# USB_Hub.net
KiCad netlist of a schematic drawn in EAGLE
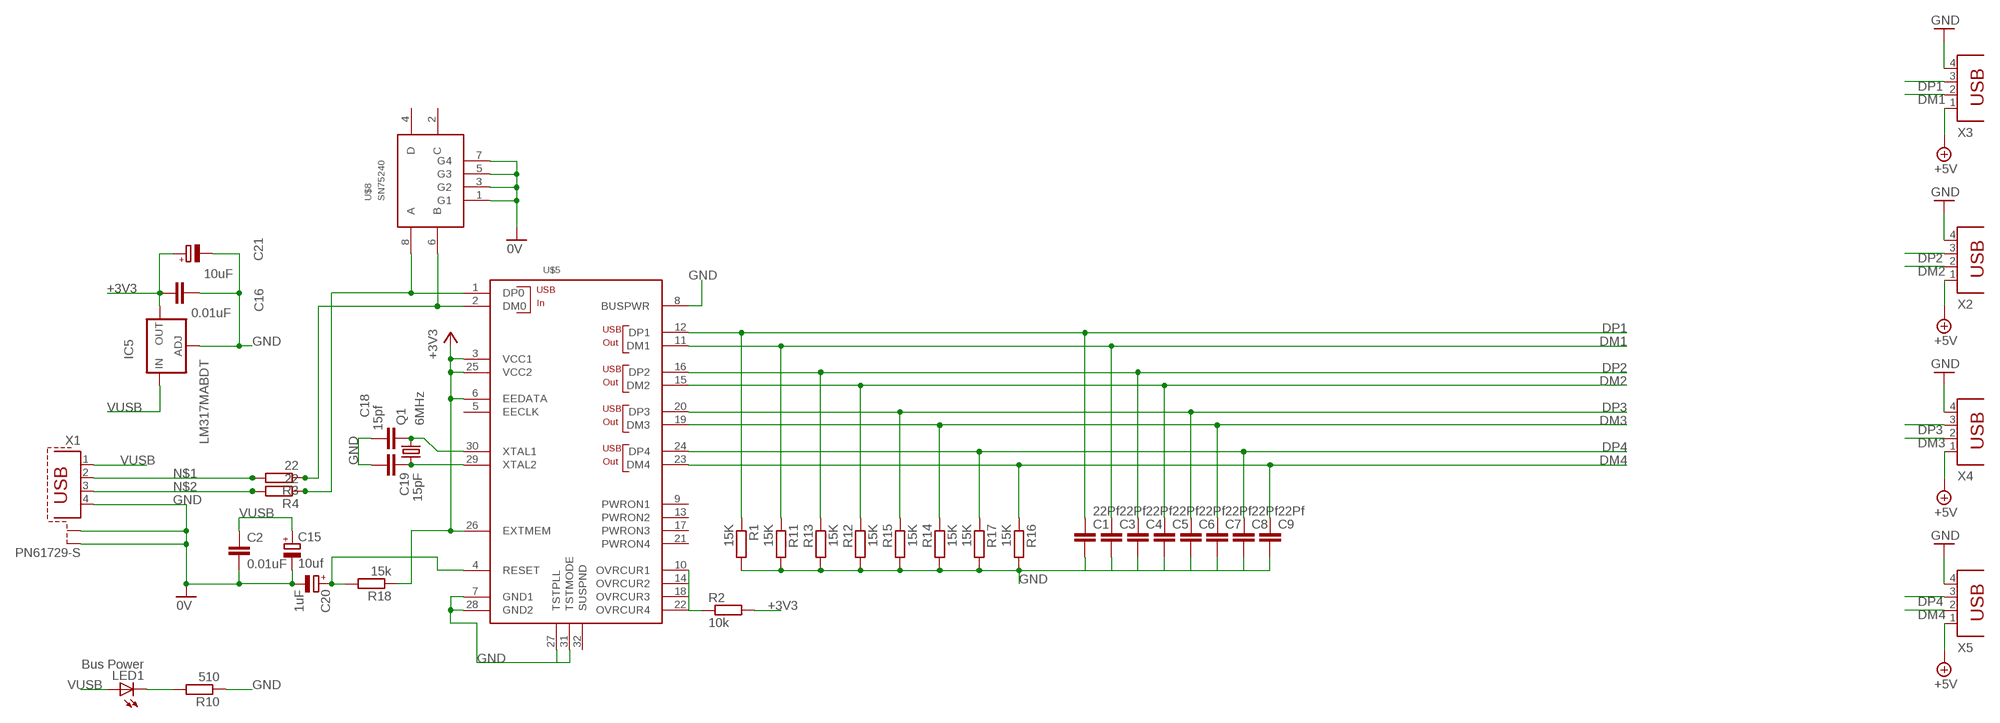
[diagram p0: schematic, sheet 1]

(export (version "E")
  (design (tool "Eeschema 10.0.6"))
  (components
    (comp (ref "C1")
      (value "22Pf")
      (footprint "eagle-import:C0805")
      (libsource (lib "eagle-import") (part "C-EUC0805"))
    )
    (comp (ref "C2")
      (value "0.01uF")
      (footprint "eagle-import:C0805")
      (libsource (lib "eagle-import") (part "C-EUC0805"))
    )
    (comp (ref "C3")
      (value "22Pf")
      (footprint "eagle-import:C0805")
      (libsource (lib "eagle-import") (part "C-EUC0805"))
    )
    (comp (ref "C4")
      (value "22Pf")
      (footprint "eagle-import:C0805")
      (libsource (lib "eagle-import") (part "C-EUC0805"))
    )
    (comp (ref "C5")
      (value "22Pf")
      (footprint "eagle-import:C0805")
      (libsource (lib "eagle-import") (part "C-EUC0805"))
    )
    (comp (ref "C6")
      (value "22Pf")
      (footprint "eagle-import:C0805")
      (libsource (lib "eagle-import") (part "C-EUC0805"))
    )
    (comp (ref "C7")
      (value "22Pf")
      (footprint "eagle-import:C0805")
      (libsource (lib "eagle-import") (part "C-EUC0805"))
    )
    (comp (ref "C8")
      (value "22Pf")
      (footprint "eagle-import:C0805")
      (libsource (lib "eagle-import") (part "C-EUC0805"))
    )
    (comp (ref "C9")
      (value "22Pf")
      (footprint "eagle-import:C0805")
      (libsource (lib "eagle-import") (part "C-EUC0805"))
    )
    (comp (ref "C15")
      (value "10uf")
      (footprint "eagle-import:E2,5-6")
      (libsource (lib "eagle-import") (part "CPOL-EUE2.5-6"))
    )
    (comp (ref "C16")
      (value "0.01uF")
      (footprint "eagle-import:C0805")
      (libsource (lib "eagle-import") (part "C-EUC0805"))
    )
    (comp (ref "C18")
      (value "15pf")
      (footprint "eagle-import:C0805")
      (libsource (lib "eagle-import") (part "C-EUC0805"))
    )
    (comp (ref "C19")
      (value "15pF")
      (footprint "eagle-import:C0805")
      (libsource (lib "eagle-import") (part "C-EUC0805"))
    )
    (comp (ref "C20")
      (value "1uF")
      (footprint "eagle-import:E2,5-6")
      (libsource (lib "eagle-import") (part "CPOL-EUE2.5-6"))
    )
    (comp (ref "C21")
      (value "10uF")
      (footprint "eagle-import:E2,5-6")
      (libsource (lib "eagle-import") (part "CPOL-EUE2.5-6"))
    )
    (comp (ref "IC5")
      (value "LM317MABDT")
      (footprint "eagle-import:DPACK")
      (libsource (lib "eagle-import") (part "v-reg_LM317?MABDT"))
    )
    (comp (ref "LED1")
      (value "Bus Power")
      (footprint "eagle-import:CHIP-LED0805")
      (libsource (lib "eagle-import") (part "LEDCHIP-LED0805"))
    )
    (comp (ref "Q1")
      (value "6MHz")
      (footprint "eagle-import:HC49UP")
      (libsource (lib "eagle-import") (part "CRYSTALHC49UP"))
    )
    (comp (ref "R1")
      (value "15K")
      (footprint "eagle-import:R0805")
      (libsource (lib "eagle-import") (part "R-EU_R0805"))
    )
    (comp (ref "R2")
      (value "10k")
      (footprint "eagle-import:R0805")
      (libsource (lib "eagle-import") (part "R-EU_R0805"))
    )
    (comp (ref "R3")
      (value "22")
      (footprint "eagle-import:R0805")
      (libsource (lib "eagle-import") (part "R-EU_R0805"))
    )
    (comp (ref "R4")
      (value "22")
      (footprint "eagle-import:R0805")
      (libsource (lib "eagle-import") (part "R-EU_R0805"))
    )
    (comp (ref "R10")
      (value "510")
      (footprint "eagle-import:R0805")
      (libsource (lib "eagle-import") (part "R-EU_R0805"))
    )
    (comp (ref "R11")
      (value "15K")
      (footprint "eagle-import:R0805")
      (libsource (lib "eagle-import") (part "R-EU_R0805"))
    )
    (comp (ref "R12")
      (value "15K")
      (footprint "eagle-import:R0805")
      (libsource (lib "eagle-import") (part "R-EU_R0805"))
    )
    (comp (ref "R13")
      (value "15K")
      (footprint "eagle-import:R0805")
      (libsource (lib "eagle-import") (part "R-EU_R0805"))
    )
    (comp (ref "R14")
      (value "15K")
      (footprint "eagle-import:R0805")
      (libsource (lib "eagle-import") (part "R-EU_R0805"))
    )
    (comp (ref "R15")
      (value "15K")
      (footprint "eagle-import:R0805")
      (libsource (lib "eagle-import") (part "R-EU_R0805"))
    )
    (comp (ref "R16")
      (value "15K")
      (footprint "eagle-import:R0805")
      (libsource (lib "eagle-import") (part "R-EU_R0805"))
    )
    (comp (ref "R17")
      (value "15K")
      (footprint "eagle-import:R0805")
      (libsource (lib "eagle-import") (part "R-EU_R0805"))
    )
    (comp (ref "R18")
      (value "15k")
      (footprint "eagle-import:R0805")
      (libsource (lib "eagle-import") (part "R-EU_R0805"))
    )
    (comp (ref "U$5")
      (value "TUSB2046")
      (footprint "eagle-import:LQFP-32")
      (libsource (lib "eagle-import") (part "TUSB2046"))
    )
    (comp (ref "U$8")
      (value "SN75240")
      (footprint "eagle-import:TSSOP8")
      (libsource (lib "eagle-import") (part "SN75240"))
    )
    (comp (ref "X1")
      (value "PN61729-S")
      (footprint "eagle-import:PN61729-S")
      (libsource (lib "eagle-import") (part "PN61729-S"))
    )
    (comp (ref "X2")
      (value "PN87520")
      (footprint "eagle-import:PN87520")
      (libsource (lib "eagle-import") (part "PN87520"))
    )
    (comp (ref "X3")
      (value "PN87520")
      (footprint "eagle-import:PN87520")
      (libsource (lib "eagle-import") (part "PN87520"))
    )
    (comp (ref "X4")
      (value "PN87520")
      (footprint "eagle-import:PN87520")
      (libsource (lib "eagle-import") (part "PN87520"))
    )
    (comp (ref "X5")
      (value "PN87520")
      (footprint "eagle-import:PN87520")
      (libsource (lib "eagle-import") (part "PN87520"))
    )
  )
  (nets
    (net (code "1") (name "+3V3") (class "Default")
      (node (ref "C16") (pin "1") (pinfunction "1_1") (pintype "passive"))
      (node (ref "C21") (pin "+") (pinfunction "+_+") (pintype "passive"))
      (node (ref "IC5") (pin "4") (pinfunction "OUT_4") (pintype "passive"))
      (node (ref "R18") (pin "1") (pinfunction "1_1") (pintype "passive"))
      (node (ref "R2") (pin "2") (pinfunction "2_2") (pintype "passive"))
      (node (ref "U$5") (pin "25") (pinfunction "VCC2_25") (pintype "bidirectional"))
      (node (ref "U$5") (pin "26") (pinfunction "EXTMEM_26") (pintype "bidirectional"))
      (node (ref "U$5") (pin "3") (pinfunction "VCC1_3") (pintype "bidirectional"))
      (node (ref "U$5") (pin "6") (pinfunction "EEDATA_6") (pintype "bidirectional"))
    )
    (net (code "2") (name "+5V") (class "Default")
      (node (ref "X2") (pin "1") (pinfunction "1_1") (pintype "passive"))
      (node (ref "X3") (pin "1") (pinfunction "1_1") (pintype "passive"))
      (node (ref "X4") (pin "1") (pinfunction "1_1") (pintype "passive"))
      (node (ref "X5") (pin "1") (pinfunction "1_1") (pintype "passive"))
    )
    (net (code "3") (name "/DM1") (class "Default")
      (node (ref "C3") (pin "1") (pinfunction "1_1") (pintype "passive"))
      (node (ref "R11") (pin "1") (pinfunction "1_1") (pintype "passive"))
      (node (ref "U$5") (pin "11") (pinfunction "DM1_11") (pintype "bidirectional"))
      (node (ref "X3") (pin "2") (pinfunction "2_2") (pintype "passive"))
    )
    (net (code "4") (name "/DM2") (class "Default")
      (node (ref "C5") (pin "1") (pinfunction "1_1") (pintype "passive"))
      (node (ref "R12") (pin "1") (pinfunction "1_1") (pintype "passive"))
      (node (ref "U$5") (pin "15") (pinfunction "DM2_15") (pintype "bidirectional"))
      (node (ref "X2") (pin "2") (pinfunction "2_2") (pintype "passive"))
    )
    (net (code "5") (name "/DM3") (class "Default")
      (node (ref "C7") (pin "1") (pinfunction "1_1") (pintype "passive"))
      (node (ref "R14") (pin "1") (pinfunction "1_1") (pintype "passive"))
      (node (ref "U$5") (pin "19") (pinfunction "DM3_19") (pintype "bidirectional"))
      (node (ref "X4") (pin "2") (pinfunction "2_2") (pintype "passive"))
    )
    (net (code "6") (name "/DM4") (class "Default")
      (node (ref "C9") (pin "1") (pinfunction "1_1") (pintype "passive"))
      (node (ref "R16") (pin "1") (pinfunction "1_1") (pintype "passive"))
      (node (ref "U$5") (pin "23") (pinfunction "DM4_23") (pintype "bidirectional"))
      (node (ref "X5") (pin "2") (pinfunction "2_2") (pintype "passive"))
    )
    (net (code "7") (name "/DP1") (class "Default")
      (node (ref "C1") (pin "1") (pinfunction "1_1") (pintype "passive"))
      (node (ref "R1") (pin "1") (pinfunction "1_1") (pintype "passive"))
      (node (ref "U$5") (pin "12") (pinfunction "DP1_12") (pintype "bidirectional"))
      (node (ref "X3") (pin "3") (pinfunction "3_3") (pintype "passive"))
    )
    (net (code "8") (name "/DP2") (class "Default")
      (node (ref "C4") (pin "1") (pinfunction "1_1") (pintype "passive"))
      (node (ref "R13") (pin "1") (pinfunction "1_1") (pintype "passive"))
      (node (ref "U$5") (pin "16") (pinfunction "DP2_16") (pintype "bidirectional"))
      (node (ref "X2") (pin "3") (pinfunction "3_3") (pintype "passive"))
    )
    (net (code "9") (name "/DP3") (class "Default")
      (node (ref "C6") (pin "1") (pinfunction "1_1") (pintype "passive"))
      (node (ref "R15") (pin "1") (pinfunction "1_1") (pintype "passive"))
      (node (ref "U$5") (pin "20") (pinfunction "DP3_20") (pintype "bidirectional"))
      (node (ref "X4") (pin "3") (pinfunction "3_3") (pintype "passive"))
    )
    (net (code "10") (name "/DP4") (class "Default")
      (node (ref "C8") (pin "1") (pinfunction "1_1") (pintype "passive"))
      (node (ref "R17") (pin "1") (pinfunction "1_1") (pintype "passive"))
      (node (ref "U$5") (pin "24") (pinfunction "DP4_24") (pintype "bidirectional"))
      (node (ref "X5") (pin "3") (pinfunction "3_3") (pintype "passive"))
    )
    (net (code "11") (name "/N$1") (class "Default")
      (node (ref "R3") (pin "2") (pinfunction "2_2") (pintype "passive"))
      (node (ref "X1") (pin "2") (pinfunction "2_2") (pintype "passive"))
    )
    (net (code "12") (name "/N$2") (class "Default")
      (node (ref "R4") (pin "2") (pinfunction "2_2") (pintype "passive"))
      (node (ref "X1") (pin "3") (pinfunction "3_3") (pintype "passive"))
    )
    (net (code "13") (name "/VUSB") (class "Default")
      (node (ref "C15") (pin "+") (pinfunction "+_+") (pintype "passive"))
      (node (ref "C2") (pin "1") (pinfunction "1_1") (pintype "passive"))
      (node (ref "IC5") (pin "3") (pinfunction "IN_3") (pintype "input"))
      (node (ref "LED1") (pin "A") (pinfunction "A_A") (pintype "passive"))
      (node (ref "X1") (pin "1") (pinfunction "1_1") (pintype "passive"))
    )
    (net (code "14") (name "0V") (class "Default")
      (node (ref "C1") (pin "2") (pinfunction "2_2") (pintype "passive"))
      (node (ref "C15") (pin "-") (pinfunction "-_-") (pintype "passive"))
      (node (ref "C16") (pin "2") (pinfunction "2_2") (pintype "passive"))
      (node (ref "C18") (pin "1") (pinfunction "1_1") (pintype "passive"))
      (node (ref "C19") (pin "2") (pinfunction "2_2") (pintype "passive"))
      (node (ref "C2") (pin "2") (pinfunction "2_2") (pintype "passive"))
      (node (ref "C20") (pin "-") (pinfunction "-_-") (pintype "passive"))
      (node (ref "C21") (pin "-") (pinfunction "-_-") (pintype "passive"))
      (node (ref "C3") (pin "2") (pinfunction "2_2") (pintype "passive"))
      (node (ref "C4") (pin "2") (pinfunction "2_2") (pintype "passive"))
      (node (ref "C5") (pin "2") (pinfunction "2_2") (pintype "passive"))
      (node (ref "C6") (pin "2") (pinfunction "2_2") (pintype "passive"))
      (node (ref "C7") (pin "2") (pinfunction "2_2") (pintype "passive"))
      (node (ref "C8") (pin "2") (pinfunction "2_2") (pintype "passive"))
      (node (ref "C9") (pin "2") (pinfunction "2_2") (pintype "passive"))
      (node (ref "IC5") (pin "1") (pinfunction "ADJ_1") (pintype "input"))
      (node (ref "R1") (pin "2") (pinfunction "2_2") (pintype "passive"))
      (node (ref "R10") (pin "1") (pinfunction "1_1") (pintype "passive"))
      (node (ref "R11") (pin "2") (pinfunction "2_2") (pintype "passive"))
      (node (ref "R12") (pin "2") (pinfunction "2_2") (pintype "passive"))
      (node (ref "R13") (pin "2") (pinfunction "2_2") (pintype "passive"))
      (node (ref "R14") (pin "2") (pinfunction "2_2") (pintype "passive"))
      (node (ref "R15") (pin "2") (pinfunction "2_2") (pintype "passive"))
      (node (ref "R16") (pin "2") (pinfunction "2_2") (pintype "passive"))
      (node (ref "R17") (pin "2") (pinfunction "2_2") (pintype "passive"))
      (node (ref "U$5") (pin "27") (pinfunction "TSTPLL_27") (pintype "bidirectional"))
      (node (ref "U$5") (pin "28") (pinfunction "GND2_28") (pintype "bidirectional"))
      (node (ref "U$5") (pin "31") (pinfunction "TSTMODE_31") (pintype "bidirectional"))
      (node (ref "U$5") (pin "7") (pinfunction "GND1_7") (pintype "bidirectional"))
      (node (ref "U$5") (pin "8") (pinfunction "BUSPWR_8") (pintype "bidirectional"))
      (node (ref "U$8") (pin "1") (pinfunction "G1_1") (pintype "bidirectional"))
      (node (ref "U$8") (pin "3") (pinfunction "G2_3") (pintype "bidirectional"))
      (node (ref "U$8") (pin "5") (pinfunction "G3_5") (pintype "bidirectional"))
      (node (ref "U$8") (pin "7") (pinfunction "G4_7") (pintype "bidirectional"))
      (node (ref "X1") (pin "4") (pinfunction "4_4") (pintype "passive"))
      (node (ref "X1") (pin "S1") (pinfunction "S1_S1") (pintype "passive"))
      (node (ref "X1") (pin "S2") (pinfunction "S2_S2") (pintype "passive"))
      (node (ref "X2") (pin "4") (pinfunction "4_4") (pintype "passive"))
      (node (ref "X3") (pin "4") (pinfunction "4_4") (pintype "passive"))
      (node (ref "X4") (pin "4") (pinfunction "4_4") (pintype "passive"))
      (node (ref "X5") (pin "4") (pinfunction "4_4") (pintype "passive"))
    )
    (net (code "15") (name "Net-(LED1-PadC)") (class "Default")
      (node (ref "LED1") (pin "C") (pinfunction "C_C") (pintype "passive"))
      (node (ref "R10") (pin "2") (pinfunction "2_2") (pintype "passive"))
    )
    (net (code "16") (name "Net-(U$5-DM0)") (class "Default")
      (node (ref "R3") (pin "1") (pinfunction "1_1") (pintype "passive"))
      (node (ref "U$5") (pin "2") (pinfunction "DM0_2") (pintype "bidirectional"))
      (node (ref "U$8") (pin "6") (pinfunction "B_6") (pintype "bidirectional"))
    )
    (net (code "17") (name "Net-(U$5-DP0)") (class "Default")
      (node (ref "R4") (pin "1") (pinfunction "1_1") (pintype "passive"))
      (node (ref "U$5") (pin "1") (pinfunction "DP0_1") (pintype "bidirectional"))
      (node (ref "U$8") (pin "8") (pinfunction "A_8") (pintype "bidirectional"))
    )
    (net (code "18") (name "Net-(U$5-OVRCUR1)") (class "Default")
      (node (ref "R2") (pin "1") (pinfunction "1_1") (pintype "passive"))
      (node (ref "U$5") (pin "10") (pinfunction "OVRCUR1_10") (pintype "bidirectional"))
      (node (ref "U$5") (pin "14") (pinfunction "OVRCUR2_14") (pintype "bidirectional"))
      (node (ref "U$5") (pin "18") (pinfunction "OVRCUR3_18") (pintype "bidirectional"))
      (node (ref "U$5") (pin "22") (pinfunction "OVRCUR4_22") (pintype "bidirectional"))
    )
    (net (code "19") (name "Net-(U$5-RESET)") (class "Default")
      (node (ref "C20") (pin "+") (pinfunction "+_+") (pintype "passive"))
      (node (ref "R18") (pin "2") (pinfunction "2_2") (pintype "passive"))
      (node (ref "U$5") (pin "4") (pinfunction "RESET_4") (pintype "bidirectional"))
    )
    (net (code "20") (name "Net-(U$5-XTAL1)") (class "Default")
      (node (ref "C18") (pin "2") (pinfunction "2_2") (pintype "passive"))
      (node (ref "Q1") (pin "2") (pinfunction "2_2") (pintype "passive"))
      (node (ref "U$5") (pin "30") (pinfunction "XTAL1_30") (pintype "bidirectional"))
    )
    (net (code "21") (name "Net-(U$5-XTAL2)") (class "Default")
      (node (ref "C19") (pin "1") (pinfunction "1_1") (pintype "passive"))
      (node (ref "Q1") (pin "1") (pinfunction "1_1") (pintype "passive"))
      (node (ref "U$5") (pin "29") (pinfunction "XTAL2_29") (pintype "bidirectional"))
    )
    (net (code "22") (name "unconnected-(U$5-EECLK-Pad5)") (class "Default")
      (node (ref "U$5") (pin "5") (pinfunction "EECLK_5") (pintype "bidirectional"))
    )
    (net (code "23") (name "unconnected-(U$5-PWRON1-Pad9)") (class "Default")
      (node (ref "U$5") (pin "9") (pinfunction "PWRON1_9") (pintype "bidirectional"))
    )
    (net (code "24") (name "unconnected-(U$5-PWRON2-Pad13)") (class "Default")
      (node (ref "U$5") (pin "13") (pinfunction "PWRON2_13") (pintype "bidirectional"))
    )
    (net (code "25") (name "unconnected-(U$5-PWRON3-Pad17)") (class "Default")
      (node (ref "U$5") (pin "17") (pinfunction "PWRON3_17") (pintype "bidirectional"))
    )
    (net (code "26") (name "unconnected-(U$5-PWRON4-Pad21)") (class "Default")
      (node (ref "U$5") (pin "21") (pinfunction "PWRON4_21") (pintype "bidirectional"))
    )
    (net (code "27") (name "unconnected-(U$5-SUSPND-Pad32)") (class "Default")
      (node (ref "U$5") (pin "32") (pinfunction "SUSPND_32") (pintype "bidirectional"))
    )
    (net (code "28") (name "unconnected-(U$8-C-Pad2)") (class "Default")
      (node (ref "U$8") (pin "2") (pinfunction "C_2") (pintype "bidirectional"))
    )
    (net (code "29") (name "unconnected-(U$8-D-Pad4)") (class "Default")
      (node (ref "U$8") (pin "4") (pinfunction "D_4") (pintype "bidirectional"))
    )
  )
)
